# pixie_bottle.net
KiCad netlist of a schematic drawn in EAGLE
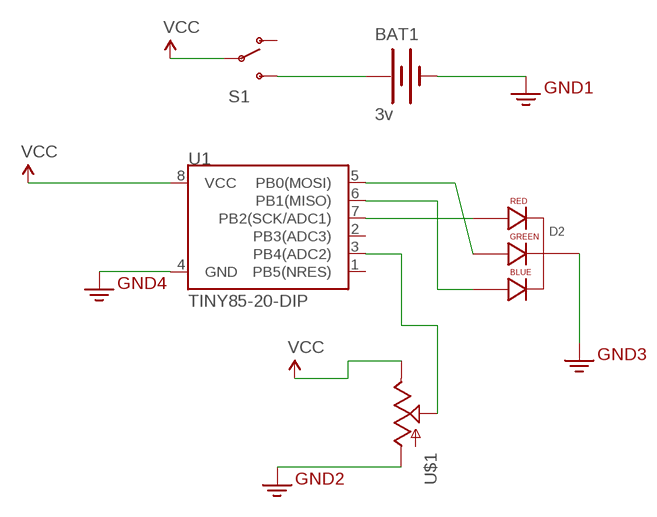
[diagram p0: schematic, sheet 1]

(export (version "E")
  (design (tool "Eeschema 10.0.6"))
  (components
    (comp (ref "BAT1")
      (value "3v")
      (footprint "eagle-import:BATTCOM_20MM_PTH")
      (libsource (lib "eagle-import") (part "BATTERY20PTH"))
    )
    (comp (ref "D2")
      (value "LED-RGB-CC-THRUDIFFUSE")
      (footprint "eagle-import:LED-RGB-THRU")
      (libsource (lib "eagle-import") (part "LED-RGB-CC-THRUDIFFUSE"))
    )
    (comp (ref "S1")
      (value "SWITCH-SPDTPTH")
      (footprint "eagle-import:SWITCH-SPDT")
      (libsource (lib "eagle-import") (part "SWITCH-SPDTPTH"))
    )
    (comp (ref "U$1")
      (value "POT-RV16AF-20")
      (footprint "eagle-import:POT_ALPHA_RV16AF-20")
      (libsource (lib "eagle-import") (part "POT-RV16AF-20"))
    )
    (comp (ref "U1")
      (value "TINY85-20-DIP")
      (footprint "eagle-import:DIP08")
      (libsource (lib "eagle-import") (part "ATTINY45TINY85-20-DIP"))
    )
  )
  (nets
    (net (code "1") (name "GND2") (class "Default")
      (node (ref "BAT1") (pin "2") (pinfunction "-_2") (pintype "power_in"))
      (node (ref "D2") (pin "2") (pinfunction "CATHODE_2") (pintype "bidirectional"))
      (node (ref "U$1") (pin "1") (pinfunction "A_1") (pintype "passive"))
      (node (ref "U1") (pin "4") (pinfunction "GND_4") (pintype "bidirectional"))
    )
    (net (code "2") (name "Net-(BAT1-+)") (class "Default")
      (node (ref "BAT1") (pin "1") (pinfunction "+_1") (pintype "power_in"))
      (node (ref "S1") (pin "3") (pinfunction "S_3") (pintype "passive"))
    )
    (net (code "3") (name "Net-(D2-BLUE_CATHODE)") (class "Default")
      (node (ref "D2") (pin "4") (pinfunction "BLUE_CATHODE_4") (pintype "bidirectional"))
      (node (ref "U1") (pin "6") (pinfunction "PB1(MISO)_6") (pintype "bidirectional"))
    )
    (net (code "4") (name "Net-(D2-GREEN_CATHODE)") (class "Default")
      (node (ref "D2") (pin "3") (pinfunction "GREEN_CATHODE_3") (pintype "bidirectional"))
      (node (ref "U1") (pin "5") (pinfunction "PB0(MOSI)_5") (pintype "bidirectional"))
    )
    (net (code "5") (name "Net-(D2-RED_CATHODE)") (class "Default")
      (node (ref "D2") (pin "1") (pinfunction "RED_CATHODE_1") (pintype "bidirectional"))
      (node (ref "U1") (pin "7") (pinfunction "PB2(SCK/ADC1)_7") (pintype "bidirectional"))
    )
    (net (code "6") (name "Net-(U$1-S)") (class "Default")
      (node (ref "U$1") (pin "2") (pinfunction "S_2") (pintype "passive"))
      (node (ref "U1") (pin "3") (pinfunction "PB4(ADC2)_3") (pintype "bidirectional"))
    )
    (net (code "7") (name "VCC") (class "Default")
      (node (ref "S1") (pin "2") (pinfunction "P_2") (pintype "passive"))
      (node (ref "U$1") (pin "3") (pinfunction "E_3") (pintype "passive"))
      (node (ref "U1") (pin "8") (pinfunction "VCC_8") (pintype "bidirectional"))
    )
    (net (code "8") (name "unconnected-(S1-O-Pad1)") (class "Default")
      (node (ref "S1") (pin "1") (pinfunction "O_1") (pintype "passive"))
    )
    (net (code "9") (name "unconnected-(U1-PB3(ADC3)-Pad2)") (class "Default")
      (node (ref "U1") (pin "2") (pinfunction "PB3(ADC3)_2") (pintype "bidirectional"))
    )
    (net (code "10") (name "unconnected-(U1-PB5(NRES)-Pad1)") (class "Default")
      (node (ref "U1") (pin "1") (pinfunction "PB5(NRES)_1") (pintype "bidirectional"))
    )
  )
)
